# USB.net
KiCad netlist of a schematic drawn in EAGLE
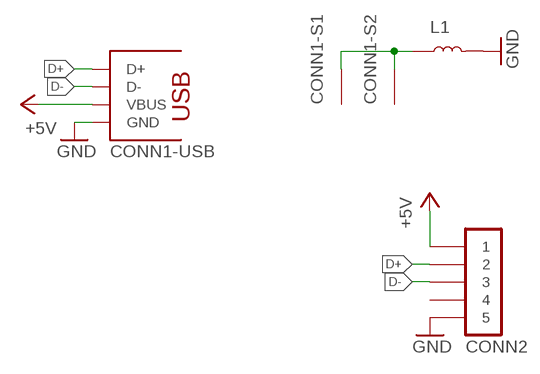
[diagram p0: schematic, sheet 1]

(export (version "E")
  (design (tool "Eeschema 10.0.6"))
  (components
    (comp (ref "CONN1")
      (value "USB-V")
      (footprint "eagle-import:USB-B-PTH-V")
      (fields (field (name "MANUFACTURER") "CUI Devices") (field (name "MPN") "UJ2-BV-1-TH"))
      (libsource (lib "eagle-import") (part "USB-V"))
    )
    (comp (ref "CONN2")
      (value "PINHD-1X05-JST-XH-H")
      (footprint "eagle-import:JST-XH-05P-H")
      (libsource (lib "eagle-import") (part "PINHD-1X05-JST-XH-H"))
    )
    (comp (ref "L1")
      (value "FERRITE_BEAD-BLM21PG221SN1D")
      (footprint "eagle-import:L0805")
      (fields (field (name "MANUFACTURER") "Murata") (field (name "MPN") "BLM21PG221SN1D"))
      (libsource (lib "eagle-import") (part "FERRITE_BEAD-BLM21PG221SN1D"))
    )
  )
  (nets
    (net (code "1") (name "+5V") (class "Default")
      (node (ref "CONN1") (pin "VBUS") (pinfunction "VBUS_VBUS") (pintype "bidirectional"))
      (node (ref "CONN2") (pin "1") (pinfunction "1_1") (pintype "passive"))
    )
    (net (code "2") (name "D+") (class "Default")
      (node (ref "CONN1") (pin "D+") (pinfunction "D+_D+") (pintype "bidirectional"))
      (node (ref "CONN2") (pin "2") (pinfunction "2_2") (pintype "passive"))
    )
    (net (code "3") (name "D-") (class "Default")
      (node (ref "CONN1") (pin "D-") (pinfunction "D-_D-") (pintype "bidirectional"))
      (node (ref "CONN2") (pin "3") (pinfunction "3_3") (pintype "passive"))
    )
    (net (code "4") (name "GND") (class "Default")
      (node (ref "CONN1") (pin "GND") (pinfunction "GND_GND") (pintype "bidirectional"))
      (node (ref "CONN2") (pin "5") (pinfunction "5_5") (pintype "passive"))
      (node (ref "L1") (pin "2") (pinfunction "2_2") (pintype "passive"))
    )
    (net (code "5") (name "Net-(CONN1A-S)") (class "Default")
      (node (ref "CONN1") (pin "S1") (pinfunction "S_S1") (pintype "passive"))
      (node (ref "CONN1") (pin "S2") (pinfunction "S_S2") (pintype "passive"))
      (node (ref "L1") (pin "1") (pinfunction "1_1") (pintype "passive"))
    )
    (net (code "6") (name "unconnected-(CONN2-Pad4)") (class "Default")
      (node (ref "CONN2") (pin "4") (pinfunction "4_4") (pintype "passive"))
    )
  )
)
